# PanelTSW.net
KiCad netlist of a schematic drawn in Altium Designer
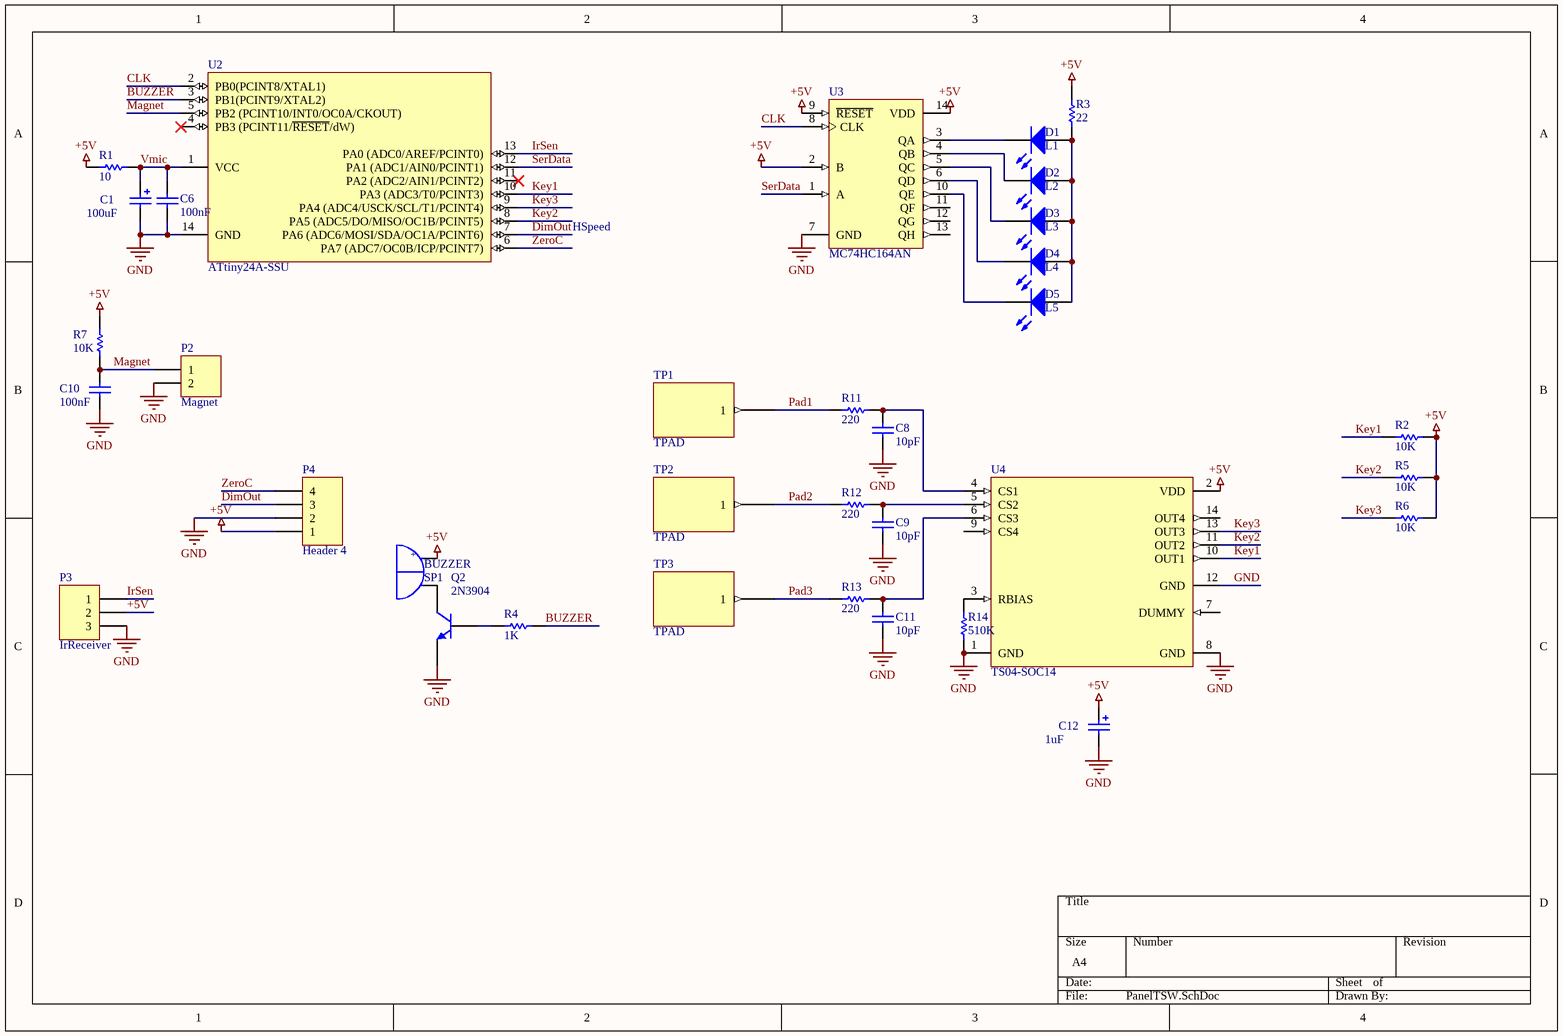
[diagram p0: PanelTSW.SchDoc]

(export (version "E")
  (design (tool "Eeschema 10.0.6"))
  (components
    (comp (ref "C1")
      (value "100uF")
      (footprint "RB.15/.2")
      (description "Polarized Capacitor")
      (fields (field (name "PUBLISHER") "Altium Limited"))
      (libsource (lib "MySchLib") (part "Cap Pol"))
    )
    (comp (ref "C6")
      (value "100nF")
      (footprint "RAD0.2")
      (description "Capacitor")
      (fields (field (name "PUBLISHER") "Altium Limited"))
      (libsource (lib "MySchLib") (part "Cap"))
    )
    (comp (ref "C8")
      (value "10pF")
      (footprint "1206C")
      (description "Capacitor")
      (fields (field (name "PUBLISHER") "Altium Limited"))
      (libsource (lib "MySchLib") (part "Cap"))
    )
    (comp (ref "C9")
      (value "10pF")
      (footprint "1206C")
      (description "Capacitor")
      (fields (field (name "PUBLISHER") "Altium Limited"))
      (libsource (lib "MySchLib") (part "Cap"))
    )
    (comp (ref "C10")
      (value "100nF")
      (footprint "RAD0.2")
      (description "Capacitor SMD")
      (fields (field (name "PUBLISHER") "Altium Limited"))
      (libsource (lib "MySchLib") (part "Cap"))
    )
    (comp (ref "C11")
      (value "10pF")
      (footprint "1206C")
      (description "Capacitor")
      (fields (field (name "PUBLISHER") "Altium Limited"))
      (libsource (lib "MySchLib") (part "Cap"))
    )
    (comp (ref "C12")
      (value "1uF")
      (footprint "RB.15/.2")
      (description "Polarized Capacitor")
      (fields (field (name "PUBLISHER") "Altium Limited"))
      (libsource (lib "MySchLib") (part "Cap Pol"))
    )
    (comp (ref "D1")
      (value "L1")
      (footprint "1206LED")
      (description "LED Radial 0.5")
      (fields (field (name "PUBLISHER") "Altium Limited"))
      (libsource (lib "MySchLib") (part "LED0.5"))
    )
    (comp (ref "D2")
      (value "L2")
      (footprint "1206LED")
      (description "LED Radial 0.5")
      (fields (field (name "PUBLISHER") "Altium Limited"))
      (libsource (lib "MySchLib") (part "LED0.5"))
    )
    (comp (ref "D3")
      (value "L3")
      (footprint "1206LED")
      (description "LED Radial 0.5")
      (fields (field (name "PUBLISHER") "Altium Limited"))
      (libsource (lib "MySchLib") (part "LED0.5"))
    )
    (comp (ref "D4")
      (value "L4")
      (footprint "1206LED")
      (description "LED Radial 0.5")
      (fields (field (name "PUBLISHER") "Altium Limited"))
      (libsource (lib "MySchLib") (part "LED0.5"))
    )
    (comp (ref "D5")
      (value "L5")
      (footprint "1206LED")
      (description "LED Radial 0.5")
      (fields (field (name "PUBLISHER") "Altium Limited"))
      (libsource (lib "MySchLib") (part "LED0.5"))
    )
    (comp (ref "P2")
      (value "Magnet")
      (footprint "Magnet")
      (description "Header, 2-Pin")
      (fields (field (name "PUBLISHER") "Altium Limited"))
      (libsource (lib "Miscellaneous Connectors") (part "Header 2"))
    )
    (comp (ref "P3")
      (value "IrReceiver")
      (footprint "IrRec1")
      (description "3pin")
      (fields (field (name "PUBLISHER") "Altium Limited"))
      (libsource (lib "Miscellaneous Connectors") (part "Header 3"))
    )
    (comp (ref "P4")
      (value "Header 4")
      (footprint "CON4")
      (description "Header, 4-Pin")
      (fields (field (name "PUBLISHER") "Altium Limited"))
      (libsource (lib "Miscellaneous Connectors") (part "Header 4"))
    )
    (comp (ref "Q2")
      (value "2N3904")
      (footprint "TO92BS2")
      (description "NPN General Purpose Amplifier")
      (fields (field (name "PUBLISHER") "Altium Limited"))
      (libsource (lib "MySchLib") (part "BC337"))
    )
    (comp (ref "R1")
      (value "10")
      (footprint "RES0.35")
      (description "Resistor")
      (fields (field (name "PUBLISHER") "Altium Limited"))
      (libsource (lib "MySchLib") (part "Resistor"))
    )
    (comp (ref "R2")
      (value "10K")
      (footprint "1206R")
      (description "Resistor")
      (fields (field (name "PUBLISHER") "Altium Limited"))
      (libsource (lib "MySchLib") (part "Resistor"))
    )
    (comp (ref "R3")
      (value "22")
      (footprint "RES0.35")
      (description "Resistor")
      (fields (field (name "PUBLISHER") "Altium Limited"))
      (libsource (lib "MySchLib") (part "Resistor"))
    )
    (comp (ref "R4")
      (value "1K")
      (footprint "1206R")
      (description "Resistor")
      (fields (field (name "PUBLISHER") "Altium Limited"))
      (libsource (lib "") (part "Resistor_1"))
    )
    (comp (ref "R5")
      (value "10K")
      (footprint "1206R")
      (description "Resistor")
      (fields (field (name "PUBLISHER") "Altium Limited"))
      (libsource (lib "MySchLib") (part "Resistor"))
    )
    (comp (ref "R6")
      (value "10K")
      (footprint "1206R")
      (description "Resistor")
      (fields (field (name "PUBLISHER") "Altium Limited"))
      (libsource (lib "MySchLib") (part "Resistor"))
    )
    (comp (ref "R7")
      (value "10K")
      (footprint "RES0.35")
      (description "Resistor")
      (fields (field (name "PUBLISHER") "Altium Limited"))
      (libsource (lib "MySchLib") (part "Resistor"))
    )
    (comp (ref "R11")
      (value "220")
      (footprint "1206R")
      (description "Resistor")
      (fields (field (name "PUBLISHER") "Altium Limited"))
      (libsource (lib "MySchLib") (part "Resistor"))
    )
    (comp (ref "R12")
      (value "220")
      (footprint "1206R")
      (description "Resistor")
      (fields (field (name "PUBLISHER") "Altium Limited"))
      (libsource (lib "MySchLib") (part "Resistor"))
    )
    (comp (ref "R13")
      (value "220")
      (footprint "1206R")
      (description "Resistor")
      (fields (field (name "PUBLISHER") "Altium Limited"))
      (libsource (lib "MySchLib") (part "Resistor"))
    )
    (comp (ref "R14")
      (value "510K")
      (footprint "1206R")
      (description "Resistor")
      (fields (field (name "PUBLISHER") "Altium Limited"))
      (libsource (lib "MySchLib") (part "Resistor"))
    )
    (comp (ref "SP1")
      (value "BUZZER")
      (footprint "RB.3/.6")
      (description "5Volt")
      (libsource (lib "MySchLib") (part "BUZZER"))
    )
    (comp (ref "TP1")
      (value "TPAD")
      (footprint "TPAD14x7")
      (description "Touch Pad")
      (libsource (lib "MySchLib") (part "PAD14x7"))
    )
    (comp (ref "TP2")
      (value "TPAD")
      (footprint "TPAD14x7")
      (description "Touch Pad")
      (libsource (lib "MySchLib") (part "PAD14x7"))
    )
    (comp (ref "TP3")
      (value "TPAD")
      (footprint "TPAD14x7")
      (description "Touch Pad")
      (libsource (lib "MySchLib") (part "PAD14x7"))
    )
    (comp (ref "U2")
      (value "ATtiny24A-SSU")
      (footprint "SOIC14")
      (description "8-Bit AVR Microcontroller with 2K Bytes of Flash Memory")
      (fields (field (name "PUBLISHER") "Altium Limited"))
      (libsource (lib "MySchLib") (part "ATtiny24-16PC"))
    )
    (comp (ref "U3")
      (value "MC74HC164AN")
      (footprint "SOIC14")
      (description "8-Bit Serial Input / Parallel-Output Shift Register")
      (fields (field (name "PUBLISHER") "Altium Limited"))
      (libsource (lib "ON Semi Logic Register") (part "MC74HC164AN"))
    )
    (comp (ref "U4")
      (value "TS04-SOC14")
      (footprint "SOIC14")
      (description "Touch swith")
      (fields (field (name "PUBLISHER") "Altium Limited"))
      (libsource (lib "MySchLib") (part "TS04"))
    )
  )
  (nets
    (net (code "1") (name "+5V") (class "Default")
      (node (ref "C12") (pin "1") (pinfunction "1_1") (pintype "passive"))
      (node (ref "P3") (pin "2") (pinfunction "2_2") (pintype "passive"))
      (node (ref "P4") (pin "1") (pinfunction "1_1") (pintype "passive"))
      (node (ref "R1") (pin "2") (pinfunction "2_2") (pintype "passive"))
      (node (ref "R2") (pin "1") (pinfunction "1_1") (pintype "passive"))
      (node (ref "R3") (pin "1") (pinfunction "1_1") (pintype "passive"))
      (node (ref "R5") (pin "1") (pinfunction "1_1") (pintype "passive"))
      (node (ref "R6") (pin "1") (pinfunction "1_1") (pintype "passive"))
      (node (ref "R7") (pin "2") (pinfunction "2_2") (pintype "passive"))
      (node (ref "SP1") (pin "1") (pinfunction "1_1") (pintype "passive"))
      (node (ref "U3") (pin "14") (pinfunction "VDD_14") (pintype "power_in"))
      (node (ref "U3") (pin "2") (pinfunction "B_2") (pintype "input"))
      (node (ref "U3") (pin "9") (pinfunction "~{RESET}_9") (pintype "input"))
      (node (ref "U4") (pin "2") (pinfunction "VDD_2") (pintype "power_in"))
    )
    (net (code "2") (name "/BUZZER") (class "Default")
      (node (ref "R4") (pin "1") (pinfunction "1_1") (pintype "passive"))
      (node (ref "U2") (pin "3") (pinfunction "PB1(PCINT9/XTAL2)_3") (pintype "bidirectional"))
    )
    (net (code "3") (name "/CLK") (class "Default")
      (node (ref "U2") (pin "2") (pinfunction "PB0(PCINT8/XTAL1)_2") (pintype "bidirectional"))
      (node (ref "U3") (pin "8") (pinfunction "CLK_8") (pintype "input"))
    )
    (net (code "4") (name "/DimOut") (class "Default")
      (node (ref "P4") (pin "3") (pinfunction "3_3") (pintype "passive"))
      (node (ref "U2") (pin "7") (pinfunction "PA6_(ADC6/MOSI/SDA/OC1A/PCINT6)_7") (pintype "bidirectional"))
    )
    (net (code "5") (name "/IrSen") (class "Default")
      (node (ref "P3") (pin "1") (pinfunction "1_1") (pintype "passive"))
      (node (ref "U2") (pin "13") (pinfunction "PA0_(ADC0/AREF/PCINT0)_13") (pintype "bidirectional"))
    )
    (net (code "6") (name "/Key1") (class "Default")
      (node (ref "R2") (pin "2") (pinfunction "2_2") (pintype "passive"))
      (node (ref "U2") (pin "10") (pinfunction "PA3_(ADC3/T0/PCINT3)_10") (pintype "bidirectional"))
      (node (ref "U4") (pin "10") (pinfunction "OUT1_10") (pintype "output"))
    )
    (net (code "7") (name "/Key2") (class "Default")
      (node (ref "R5") (pin "2") (pinfunction "2_2") (pintype "passive"))
      (node (ref "U2") (pin "8") (pinfunction "PA5_(ADC5/DO/MISO/OC1B/PCINT5)_8") (pintype "bidirectional"))
      (node (ref "U4") (pin "11") (pinfunction "OUT2_11") (pintype "output"))
    )
    (net (code "8") (name "/Key3") (class "Default")
      (node (ref "R6") (pin "2") (pinfunction "2_2") (pintype "passive"))
      (node (ref "U2") (pin "9") (pinfunction "PA4_(ADC4/USCK/SCL/T1/PCINT4)_9") (pintype "bidirectional"))
      (node (ref "U4") (pin "13") (pinfunction "OUT3_13") (pintype "output"))
    )
    (net (code "9") (name "/Magnet") (class "Default")
      (node (ref "C10") (pin "2") (pinfunction "2_2") (pintype "passive"))
      (node (ref "P2") (pin "1") (pinfunction "1_1") (pintype "passive"))
      (node (ref "R7") (pin "1") (pinfunction "1_1") (pintype "passive"))
      (node (ref "U2") (pin "5") (pinfunction "PB2_(PCINT10/INT0/OC0A/CKOUT)_5") (pintype "bidirectional"))
    )
    (net (code "10") (name "/Pad1") (class "Default")
      (node (ref "R11") (pin "2") (pinfunction "2_2") (pintype "passive"))
      (node (ref "TP1") (pin "1") (pinfunction "1_1") (pintype "output"))
    )
    (net (code "11") (name "/Pad2") (class "Default")
      (node (ref "R12") (pin "2") (pinfunction "2_2") (pintype "passive"))
      (node (ref "TP2") (pin "1") (pinfunction "1_1") (pintype "output"))
    )
    (net (code "12") (name "/Pad3") (class "Default")
      (node (ref "R13") (pin "2") (pinfunction "2_2") (pintype "passive"))
      (node (ref "TP3") (pin "1") (pinfunction "1_1") (pintype "output"))
    )
    (net (code "13") (name "/SerData") (class "Default")
      (node (ref "U2") (pin "12") (pinfunction "PA1_(ADC1/AIN0/PCINT1)_12") (pintype "bidirectional"))
      (node (ref "U3") (pin "1") (pinfunction "A_1") (pintype "input"))
    )
    (net (code "14") (name "/Vmic") (class "Default")
      (node (ref "C1") (pin "1") (pinfunction "1_1") (pintype "passive"))
      (node (ref "C6") (pin "2") (pinfunction "2_2") (pintype "passive"))
      (node (ref "R1") (pin "1") (pinfunction "1_1") (pintype "passive"))
      (node (ref "U2") (pin "1") (pinfunction "VCC_1") (pintype "power_in"))
    )
    (net (code "15") (name "/ZeroC") (class "Default")
      (node (ref "P4") (pin "4") (pinfunction "4_4") (pintype "passive"))
      (node (ref "U2") (pin "6") (pinfunction "PA7_(ADC7/OC0B/ICP/PCINT7)_6") (pintype "bidirectional"))
    )
    (net (code "16") (name "GND") (class "Default")
      (node (ref "C1") (pin "2") (pinfunction "2_2") (pintype "passive"))
      (node (ref "C10") (pin "1") (pinfunction "1_1") (pintype "passive"))
      (node (ref "C11") (pin "1") (pinfunction "1_1") (pintype "passive"))
      (node (ref "C12") (pin "2") (pinfunction "2_2") (pintype "passive"))
      (node (ref "C6") (pin "1") (pinfunction "1_1") (pintype "passive"))
      (node (ref "C8") (pin "1") (pinfunction "1_1") (pintype "passive"))
      (node (ref "C9") (pin "1") (pinfunction "1_1") (pintype "passive"))
      (node (ref "P2") (pin "2") (pinfunction "2_2") (pintype "passive"))
      (node (ref "P3") (pin "3") (pinfunction "3_3") (pintype "passive"))
      (node (ref "P4") (pin "2") (pinfunction "2_2") (pintype "passive"))
      (node (ref "Q2") (pin "3") (pinfunction "E_3") (pintype "passive"))
      (node (ref "R14") (pin "2") (pinfunction "2_2") (pintype "passive"))
      (node (ref "U2") (pin "14") (pinfunction "GND_14") (pintype "power_in"))
      (node (ref "U3") (pin "7") (pinfunction "GND_7") (pintype "power_in"))
      (node (ref "U4") (pin "1") (pinfunction "GND_1") (pintype "power_in"))
      (node (ref "U4") (pin "12") (pinfunction "GND_12") (pintype "power_in"))
      (node (ref "U4") (pin "8") (pinfunction "GND_8") (pintype "power_in"))
    )
    (net (code "17") (name "Net-(D1-A)") (class "Default")
      (node (ref "D1") (pin "1") (pinfunction "A_1") (pintype "passive"))
      (node (ref "D2") (pin "1") (pinfunction "A_1") (pintype "passive"))
      (node (ref "D3") (pin "1") (pinfunction "A_1") (pintype "passive"))
      (node (ref "D4") (pin "1") (pinfunction "A_1") (pintype "passive"))
      (node (ref "D5") (pin "1") (pinfunction "A_1") (pintype "passive"))
      (node (ref "R3") (pin "2") (pinfunction "2_2") (pintype "passive"))
    )
    (net (code "18") (name "Net-(D1-K)") (class "Default")
      (node (ref "D1") (pin "2") (pinfunction "K_2") (pintype "passive"))
      (node (ref "U3") (pin "3") (pinfunction "QA_3") (pintype "output"))
    )
    (net (code "19") (name "Net-(D2-K)") (class "Default")
      (node (ref "D2") (pin "2") (pinfunction "K_2") (pintype "passive"))
      (node (ref "U3") (pin "4") (pinfunction "QB_4") (pintype "output"))
    )
    (net (code "20") (name "Net-(D3-K)") (class "Default")
      (node (ref "D3") (pin "2") (pinfunction "K_2") (pintype "passive"))
      (node (ref "U3") (pin "5") (pinfunction "QC_5") (pintype "output"))
    )
    (net (code "21") (name "Net-(D4-K)") (class "Default")
      (node (ref "D4") (pin "2") (pinfunction "K_2") (pintype "passive"))
      (node (ref "U3") (pin "6") (pinfunction "QD_6") (pintype "output"))
    )
    (net (code "22") (name "Net-(D5-K)") (class "Default")
      (node (ref "D5") (pin "2") (pinfunction "K_2") (pintype "passive"))
      (node (ref "U3") (pin "10") (pinfunction "QE_10") (pintype "output"))
    )
    (net (code "23") (name "Net-(Q2-B)") (class "Default")
      (node (ref "Q2") (pin "1") (pinfunction "B_1") (pintype "passive"))
      (node (ref "R4") (pin "2") (pinfunction "2_2") (pintype "passive"))
    )
    (net (code "24") (name "Net-(Q2-C)") (class "Default")
      (node (ref "Q2") (pin "2") (pinfunction "C_2") (pintype "passive"))
      (node (ref "SP1") (pin "2") (pinfunction "2_2") (pintype "passive"))
    )
    (net (code "25") (name "Net-(U4-CS1)") (class "Default")
      (node (ref "C8") (pin "2") (pinfunction "2_2") (pintype "passive"))
      (node (ref "R11") (pin "1") (pinfunction "1_1") (pintype "passive"))
      (node (ref "U4") (pin "4") (pinfunction "CS1_4") (pintype "input"))
    )
    (net (code "26") (name "Net-(U4-CS2)") (class "Default")
      (node (ref "C9") (pin "2") (pinfunction "2_2") (pintype "passive"))
      (node (ref "R12") (pin "1") (pinfunction "1_1") (pintype "passive"))
      (node (ref "U4") (pin "5") (pinfunction "CS2_5") (pintype "input"))
    )
    (net (code "27") (name "Net-(U4-CS3)") (class "Default")
      (node (ref "C11") (pin "2") (pinfunction "2_2") (pintype "passive"))
      (node (ref "R13") (pin "1") (pinfunction "1_1") (pintype "passive"))
      (node (ref "U4") (pin "6") (pinfunction "CS3_6") (pintype "input"))
    )
    (net (code "28") (name "Net-(U4-RBIAS)") (class "Default")
      (node (ref "R14") (pin "1") (pinfunction "1_1") (pintype "passive"))
      (node (ref "U4") (pin "3") (pinfunction "RBIAS_3") (pintype "input"))
    )
    (net (code "29") (name "unconnected-(U2-PA2_(ADC2{slash}AIN1{slash}PCINT2)-Pad11)") (class "Default")
      (node (ref "U2") (pin "11") (pinfunction "PA2_(ADC2/AIN1/PCINT2)_11") (pintype "bidirectional+no_connect"))
    )
    (net (code "30") (name "unconnected-(U2-PB3_(PCINT11{slash}~{RESET}{slash}dW)-Pad4)") (class "Default")
      (node (ref "U2") (pin "4") (pinfunction "PB3_(PCINT11/~{RESET}/dW)_4") (pintype "bidirectional+no_connect"))
    )
    (net (code "31") (name "unconnected-(U3-QF-Pad11)") (class "Default")
      (node (ref "U3") (pin "11") (pinfunction "QF_11") (pintype "output"))
    )
    (net (code "32") (name "unconnected-(U3-QG-Pad12)") (class "Default")
      (node (ref "U3") (pin "12") (pinfunction "QG_12") (pintype "output"))
    )
    (net (code "33") (name "unconnected-(U3-QH-Pad13)") (class "Default")
      (node (ref "U3") (pin "13") (pinfunction "QH_13") (pintype "output"))
    )
    (net (code "34") (name "unconnected-(U4-CS4-Pad9)") (class "Default")
      (node (ref "U4") (pin "9") (pinfunction "CS4_9") (pintype "input"))
    )
    (net (code "35") (name "unconnected-(U4-DUMMY-Pad7)") (class "Default")
      (node (ref "U4") (pin "7") (pinfunction "DUMMY_7") (pintype "input"))
    )
    (net (code "36") (name "unconnected-(U4-OUT4-Pad14)") (class "Default")
      (node (ref "U4") (pin "14") (pinfunction "OUT4_14") (pintype "output"))
    )
  )
)
